# lcd_key.net
KiCad netlist of a schematic drawn in Altium Designer
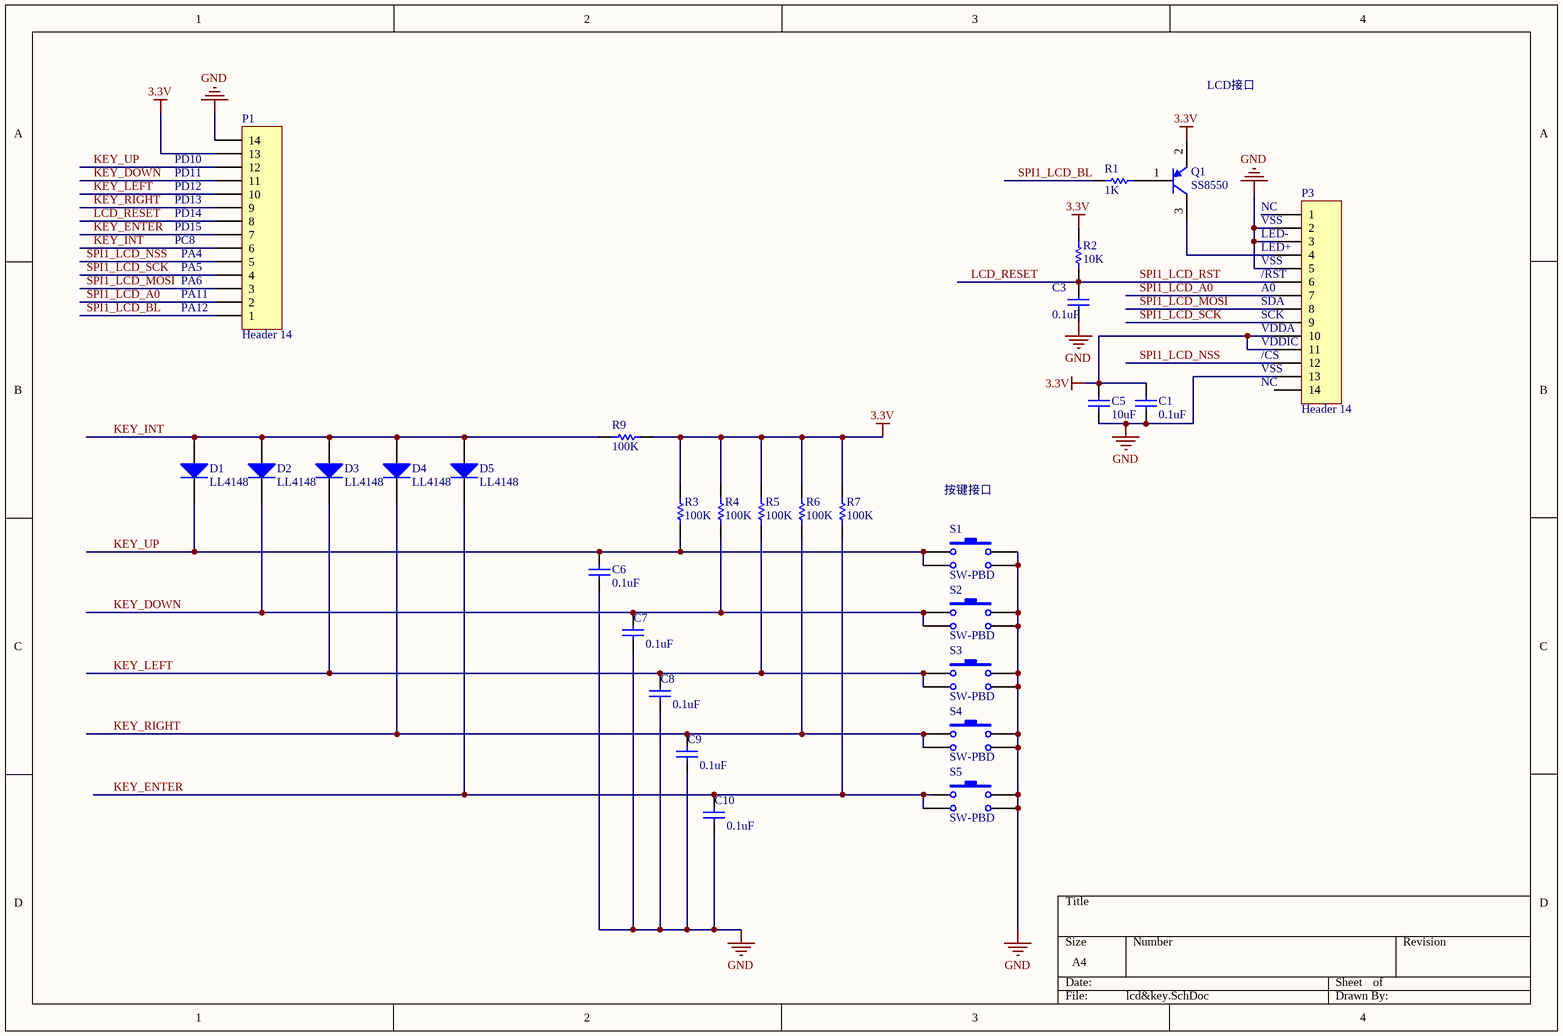
[diagram p0: lcd&key.SchDoc]

(export (version "E")
  (design (tool "Eeschema 10.0.6"))
  (components
    (comp (ref "C1")
      (value "0.1uF")
      (footprint "CAPC2012M")
      (description "Capacitor")
      (fields (field (name "PUBLISHER") "Altium Limited"))
      (libsource (lib "Miscellaneous Devices") (part "Cap"))
    )
    (comp (ref "C3")
      (value "0.1uF")
      (footprint "CAPC2012M")
      (description "Capacitor")
      (fields (field (name "PUBLISHER") "Altium Limited"))
      (libsource (lib "Miscellaneous Devices") (part "Cap"))
    )
    (comp (ref "C5")
      (value "10uF")
      (footprint "CAPC2012M")
      (description "Capacitor")
      (fields (field (name "PUBLISHER") "Altium Limited"))
      (libsource (lib "Miscellaneous Devices") (part "Cap"))
    )
    (comp (ref "C6")
      (value "0.1uF")
      (footprint "CAPC2012M")
      (description "Capacitor")
      (fields (field (name "PUBLISHER") "Altium Limited"))
      (libsource (lib "Miscellaneous Devices") (part "Cap"))
    )
    (comp (ref "C7")
      (value "0.1uF")
      (footprint "CAPC2012M")
      (description "Capacitor")
      (fields (field (name "PUBLISHER") "Altium Limited"))
      (libsource (lib "Miscellaneous Devices") (part "Cap"))
    )
    (comp (ref "C8")
      (value "0.1uF")
      (footprint "CAPC2012M")
      (description "Capacitor")
      (fields (field (name "PUBLISHER") "Altium Limited"))
      (libsource (lib "Miscellaneous Devices") (part "Cap"))
    )
    (comp (ref "C9")
      (value "0.1uF")
      (footprint "CAPC2012M")
      (description "Capacitor")
      (fields (field (name "PUBLISHER") "Altium Limited"))
      (libsource (lib "Miscellaneous Devices") (part "Cap"))
    )
    (comp (ref "C10")
      (value "0.1uF")
      (footprint "CAPC2012M")
      (description "Capacitor")
      (fields (field (name "PUBLISHER") "Altium Limited"))
      (libsource (lib "Miscellaneous Devices") (part "Cap"))
    )
    (comp (ref "D1")
      (value "LL4148")
      (footprint "CD2012-0805")
      (description "1 Amp General Purpose Rectifier")
      (fields (field (name "PUBLISHER") "Altium Limited"))
      (libsource (lib "Miscellaneous Devices") (part "Diode 1N4007"))
    )
    (comp (ref "D2")
      (value "LL4148")
      (footprint "CD2012-0805")
      (description "1 Amp General Purpose Rectifier")
      (fields (field (name "PUBLISHER") "Altium Limited"))
      (libsource (lib "Miscellaneous Devices") (part "Diode 1N4007"))
    )
    (comp (ref "D3")
      (value "LL4148")
      (footprint "CD2012-0805")
      (description "1 Amp General Purpose Rectifier")
      (fields (field (name "PUBLISHER") "Altium Limited"))
      (libsource (lib "Miscellaneous Devices") (part "Diode 1N4007"))
    )
    (comp (ref "D4")
      (value "LL4148")
      (footprint "CD2012-0805")
      (description "1 Amp General Purpose Rectifier")
      (fields (field (name "PUBLISHER") "Altium Limited"))
      (libsource (lib "Miscellaneous Devices") (part "Diode 1N4007"))
    )
    (comp (ref "D5")
      (value "LL4148")
      (footprint "CD2012-0805")
      (description "1 Amp General Purpose Rectifier")
      (fields (field (name "PUBLISHER") "Altium Limited"))
      (libsource (lib "Miscellaneous Devices") (part "Diode 1N4007"))
    )
    (comp (ref "P1")
      (value "Header 14")
      (footprint "FPC0.5-14P-A")
      (description "Header, 14-Pin")
      (fields (field (name "PUBLISHER") "Altium Limited"))
      (libsource (lib "UserSchCon") (part "Header 14"))
    )
    (comp (ref "P3")
      (value "Header 14")
      (footprint "FPC14")
      (description "Header, 14-Pin")
      (fields (field (name "PUBLISHER") "Altium Limited"))
      (libsource (lib "Miscellaneous Connectors") (part "Header 14"))
    )
    (comp (ref "Q1")
      (value "SS8550")
      (footprint "SOT-23_N")
      (description "PNP General Purpose Amplifier")
      (fields (field (name "PUBLISHER") "Altium Limited"))
      (libsource (lib "Miscellaneous Devices") (part "2N3906"))
    )
    (comp (ref "R1")
      (value "1K")
      (footprint "RESC2012M")
      (description "Resistor")
      (fields (field (name "PUBLISHER") "Altium Limited"))
      (libsource (lib "Miscellaneous Devices") (part "Res1"))
    )
    (comp (ref "R2")
      (value "10K")
      (footprint "RESC2012M")
      (description "Resistor")
      (fields (field (name "PUBLISHER") "Altium Limited"))
      (libsource (lib "Miscellaneous Devices") (part "Res1"))
    )
    (comp (ref "R3")
      (value "100K")
      (footprint "RESC2012M")
      (description "Resistor")
      (fields (field (name "PUBLISHER") "Altium Limited"))
      (libsource (lib "Miscellaneous Devices") (part "Res1"))
    )
    (comp (ref "R4")
      (value "100K")
      (footprint "RESC2012M")
      (description "Resistor")
      (fields (field (name "PUBLISHER") "Altium Limited"))
      (libsource (lib "Miscellaneous Devices") (part "Res1"))
    )
    (comp (ref "R5")
      (value "100K")
      (footprint "RESC2012M")
      (description "Resistor")
      (fields (field (name "PUBLISHER") "Altium Limited"))
      (libsource (lib "Miscellaneous Devices") (part "Res1"))
    )
    (comp (ref "R6")
      (value "100K")
      (footprint "RESC2012M")
      (description "Resistor")
      (fields (field (name "PUBLISHER") "Altium Limited"))
      (libsource (lib "Miscellaneous Devices") (part "Res1"))
    )
    (comp (ref "R7")
      (value "100K")
      (footprint "RESC2012M")
      (description "Resistor")
      (fields (field (name "PUBLISHER") "Altium Limited"))
      (libsource (lib "Miscellaneous Devices") (part "Res1"))
    )
    (comp (ref "R9")
      (value "100K")
      (footprint "RESC2012M")
      (description "Resistor")
      (fields (field (name "PUBLISHER") "Altium Limited"))
      (libsource (lib "Miscellaneous Devices") (part "Res1"))
    )
    (comp (ref "S1")
      (value "SW-PBD")
      (footprint "PBDIP-4.5x4.5")
      (description "Switch")
      (fields (field (name "PUBLISHER") "Altium Limited"))
      (libsource (lib "UserSchDev") (part "SW-PBD"))
    )
    (comp (ref "S2")
      (value "SW-PBD")
      (footprint "PBDIP-4.5x4.5")
      (description "Switch")
      (fields (field (name "PUBLISHER") "Altium Limited"))
      (libsource (lib "UserSchDev") (part "SW-PBD"))
    )
    (comp (ref "S3")
      (value "SW-PBD")
      (footprint "PBDIP-4.5x4.5")
      (description "Switch")
      (fields (field (name "PUBLISHER") "Altium Limited"))
      (libsource (lib "UserSchDev") (part "SW-PBD"))
    )
    (comp (ref "S4")
      (value "SW-PBD")
      (footprint "PBDIP-4.5x4.5")
      (description "Switch")
      (fields (field (name "PUBLISHER") "Altium Limited"))
      (libsource (lib "UserSchDev") (part "SW-PBD"))
    )
    (comp (ref "S5")
      (value "SW-PBD")
      (footprint "PBDIP-4.5x4.5")
      (description "Switch")
      (fields (field (name "PUBLISHER") "Altium Limited"))
      (libsource (lib "UserSchDev") (part "SW-PBD"))
    )
  )
  (nets
    (net (code "1") (name "/KEY_DOWN") (class "Default")
      (node (ref "C7") (pin "1") (pinfunction "1_1") (pintype "passive"))
      (node (ref "D2") (pin "2") (pinfunction "K_2") (pintype "passive"))
      (node (ref "P1") (pin "11") (pinfunction "11_11") (pintype "passive"))
      (node (ref "R4") (pin "1") (pinfunction "1_1") (pintype "passive"))
      (node (ref "S2") (pin "1") (pinfunction "1_1") (pintype "passive"))
      (node (ref "S2") (pin "2") (pinfunction "2_2") (pintype "passive"))
    )
    (net (code "2") (name "/KEY_ENTER") (class "Default")
      (node (ref "C10") (pin "1") (pinfunction "1_1") (pintype "passive"))
      (node (ref "D5") (pin "2") (pinfunction "K_2") (pintype "passive"))
      (node (ref "P1") (pin "7") (pinfunction "7_7") (pintype "passive"))
      (node (ref "R7") (pin "1") (pinfunction "1_1") (pintype "passive"))
      (node (ref "S5") (pin "1") (pinfunction "1_1") (pintype "passive"))
      (node (ref "S5") (pin "2") (pinfunction "2_2") (pintype "passive"))
    )
    (net (code "3") (name "/KEY_INT") (class "Default")
      (node (ref "D1") (pin "1") (pinfunction "A_1") (pintype "passive"))
      (node (ref "D2") (pin "1") (pinfunction "A_1") (pintype "passive"))
      (node (ref "D3") (pin "1") (pinfunction "A_1") (pintype "passive"))
      (node (ref "D4") (pin "1") (pinfunction "A_1") (pintype "passive"))
      (node (ref "D5") (pin "1") (pinfunction "A_1") (pintype "passive"))
      (node (ref "P1") (pin "6") (pinfunction "6_6") (pintype "passive"))
      (node (ref "R9") (pin "1") (pinfunction "1_1") (pintype "passive"))
    )
    (net (code "4") (name "/KEY_LEFT") (class "Default")
      (node (ref "C8") (pin "1") (pinfunction "1_1") (pintype "passive"))
      (node (ref "D3") (pin "2") (pinfunction "K_2") (pintype "passive"))
      (node (ref "P1") (pin "10") (pinfunction "10_10") (pintype "passive"))
      (node (ref "R5") (pin "1") (pinfunction "1_1") (pintype "passive"))
      (node (ref "S3") (pin "1") (pinfunction "1_1") (pintype "passive"))
      (node (ref "S3") (pin "2") (pinfunction "2_2") (pintype "passive"))
    )
    (net (code "5") (name "/KEY_RIGHT") (class "Default")
      (node (ref "C9") (pin "1") (pinfunction "1_1") (pintype "passive"))
      (node (ref "D4") (pin "2") (pinfunction "K_2") (pintype "passive"))
      (node (ref "P1") (pin "9") (pinfunction "9_9") (pintype "passive"))
      (node (ref "R6") (pin "1") (pinfunction "1_1") (pintype "passive"))
      (node (ref "S4") (pin "1") (pinfunction "1_1") (pintype "passive"))
      (node (ref "S4") (pin "2") (pinfunction "2_2") (pintype "passive"))
    )
    (net (code "6") (name "/KEY_UP") (class "Default")
      (node (ref "C6") (pin "1") (pinfunction "1_1") (pintype "passive"))
      (node (ref "D1") (pin "2") (pinfunction "K_2") (pintype "passive"))
      (node (ref "P1") (pin "12") (pinfunction "12_12") (pintype "passive"))
      (node (ref "R3") (pin "1") (pinfunction "1_1") (pintype "passive"))
      (node (ref "S1") (pin "1") (pinfunction "1_1") (pintype "passive"))
      (node (ref "S1") (pin "2") (pinfunction "2_2") (pintype "passive"))
    )
    (net (code "7") (name "/LCD_RESET") (class "Default")
      (node (ref "C3") (pin "1") (pinfunction "1_1") (pintype "passive"))
      (node (ref "P1") (pin "8") (pinfunction "8_8") (pintype "passive"))
      (node (ref "P3") (pin "6") (pinfunction "6_6") (pintype "passive"))
      (node (ref "R2") (pin "2") (pinfunction "2_2") (pintype "passive"))
    )
    (net (code "8") (name "/SPI1_LCD_A0") (class "Default")
      (node (ref "P1") (pin "2") (pinfunction "2_2") (pintype "passive"))
      (node (ref "P3") (pin "7") (pinfunction "7_7") (pintype "passive"))
    )
    (net (code "9") (name "/SPI1_LCD_BL") (class "Default")
      (node (ref "P1") (pin "1") (pinfunction "1_1") (pintype "passive"))
      (node (ref "R1") (pin "2") (pinfunction "2_2") (pintype "passive"))
    )
    (net (code "10") (name "/SPI1_LCD_MOSI") (class "Default")
      (node (ref "P1") (pin "3") (pinfunction "3_3") (pintype "passive"))
      (node (ref "P3") (pin "8") (pinfunction "8_8") (pintype "passive"))
    )
    (net (code "11") (name "/SPI1_LCD_NSS") (class "Default")
      (node (ref "P1") (pin "5") (pinfunction "5_5") (pintype "passive"))
      (node (ref "P3") (pin "12") (pinfunction "12_12") (pintype "passive"))
    )
    (net (code "12") (name "/SPI1_LCD_SCK") (class "Default")
      (node (ref "P1") (pin "4") (pinfunction "4_4") (pintype "passive"))
      (node (ref "P3") (pin "9") (pinfunction "9_9") (pintype "passive"))
    )
    (net (code "13") (name "3.3V") (class "Default")
      (node (ref "C1") (pin "2") (pinfunction "2_2") (pintype "passive"))
      (node (ref "C5") (pin "2") (pinfunction "2_2") (pintype "passive"))
      (node (ref "P1") (pin "13") (pinfunction "13_13") (pintype "passive"))
      (node (ref "P3") (pin "10") (pinfunction "10_10") (pintype "passive"))
      (node (ref "P3") (pin "11") (pinfunction "11_11") (pintype "passive"))
      (node (ref "Q1") (pin "2") (pinfunction "E_2") (pintype "passive"))
      (node (ref "R2") (pin "1") (pinfunction "1_1") (pintype "passive"))
      (node (ref "R3") (pin "2") (pinfunction "2_2") (pintype "passive"))
      (node (ref "R4") (pin "2") (pinfunction "2_2") (pintype "passive"))
      (node (ref "R5") (pin "2") (pinfunction "2_2") (pintype "passive"))
      (node (ref "R6") (pin "2") (pinfunction "2_2") (pintype "passive"))
      (node (ref "R7") (pin "2") (pinfunction "2_2") (pintype "passive"))
      (node (ref "R9") (pin "2") (pinfunction "2_2") (pintype "passive"))
    )
    (net (code "14") (name "GND") (class "Default")
      (node (ref "C1") (pin "1") (pinfunction "1_1") (pintype "passive"))
      (node (ref "C10") (pin "2") (pinfunction "2_2") (pintype "passive"))
      (node (ref "C3") (pin "2") (pinfunction "2_2") (pintype "passive"))
      (node (ref "C5") (pin "1") (pinfunction "1_1") (pintype "passive"))
      (node (ref "C6") (pin "2") (pinfunction "2_2") (pintype "passive"))
      (node (ref "C7") (pin "2") (pinfunction "2_2") (pintype "passive"))
      (node (ref "C8") (pin "2") (pinfunction "2_2") (pintype "passive"))
      (node (ref "C9") (pin "2") (pinfunction "2_2") (pintype "passive"))
      (node (ref "P1") (pin "14") (pinfunction "14_14") (pintype "passive"))
      (node (ref "P3") (pin "13") (pinfunction "13_13") (pintype "passive"))
      (node (ref "P3") (pin "2") (pinfunction "2_2") (pintype "passive"))
      (node (ref "P3") (pin "3") (pinfunction "3_3") (pintype "passive"))
      (node (ref "P3") (pin "5") (pinfunction "5_5") (pintype "passive"))
      (node (ref "S1") (pin "3") (pinfunction "3_3") (pintype "passive"))
      (node (ref "S1") (pin "4") (pinfunction "4_4") (pintype "passive"))
      (node (ref "S2") (pin "3") (pinfunction "3_3") (pintype "passive"))
      (node (ref "S2") (pin "4") (pinfunction "4_4") (pintype "passive"))
      (node (ref "S3") (pin "3") (pinfunction "3_3") (pintype "passive"))
      (node (ref "S3") (pin "4") (pinfunction "4_4") (pintype "passive"))
      (node (ref "S4") (pin "3") (pinfunction "3_3") (pintype "passive"))
      (node (ref "S4") (pin "4") (pinfunction "4_4") (pintype "passive"))
      (node (ref "S5") (pin "3") (pinfunction "3_3") (pintype "passive"))
      (node (ref "S5") (pin "4") (pinfunction "4_4") (pintype "passive"))
    )
    (net (code "15") (name "Net-(Q1-B)") (class "Default")
      (node (ref "Q1") (pin "1") (pinfunction "B_1") (pintype "passive"))
      (node (ref "R1") (pin "1") (pinfunction "1_1") (pintype "passive"))
    )
    (net (code "16") (name "Net-(Q1-C)") (class "Default")
      (node (ref "P3") (pin "4") (pinfunction "4_4") (pintype "passive"))
      (node (ref "Q1") (pin "3") (pinfunction "C_3") (pintype "passive"))
    )
    (net (code "17") (name "unconnected-(P3-Pad1)") (class "Default")
      (node (ref "P3") (pin "1") (pinfunction "1_1") (pintype "passive"))
    )
    (net (code "18") (name "unconnected-(P3-Pad14)") (class "Default")
      (node (ref "P3") (pin "14") (pinfunction "14_14") (pintype "passive"))
    )
  )
)
